# RightBar2_SchDoc.net
KiCad netlist of a schematic drawn in Altium Designer
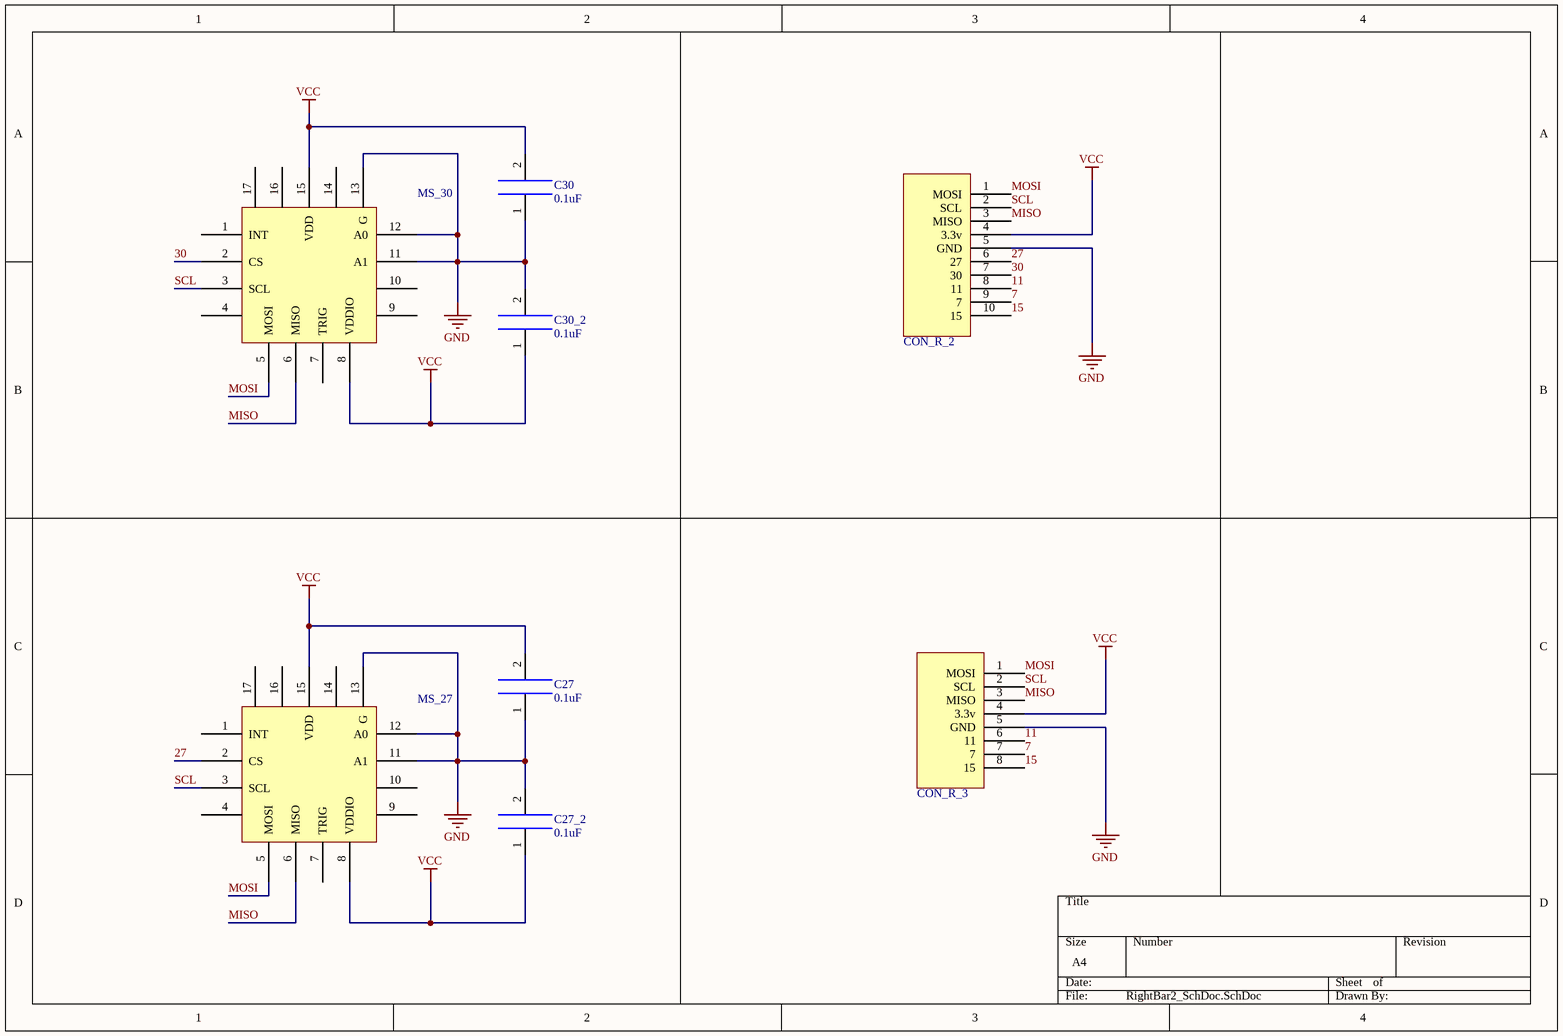
[diagram p0: RightBar2_SchDoc.SchDoc]

(export (version "E")
  (design (tool "Eeschema 10.0.6"))
  (components
    (comp (ref "C27")
      (value "0.1uF")
      (footprint "CAP_0603")
      (description "Capacitance")
      (libsource (lib "MagWaySchlib") (part "CAP"))
    )
    (comp (ref "C27_2")
      (value "0.1uF")
      (footprint "CAP_0603")
      (description "Capacitance")
      (libsource (lib "MagWaySchlib") (part "CAP"))
    )
    (comp (ref "C30")
      (value "0.1uF")
      (footprint "CAP_0603")
      (description "Capacitance")
      (libsource (lib "MagWaySchlib") (part "CAP"))
    )
    (comp (ref "C30_2")
      (value "0.1uF")
      (footprint "CAP_0603")
      (description "Capacitance")
      (libsource (lib "MagWaySchlib") (part "CAP"))
    )
    (comp (ref "CON_R_2")
      (value "PIN_right")
      (footprint "PIN_RIGHT_2")
      (libsource (lib "MagWaySchlib") (part "PIN_right_2"))
    )
    (comp (ref "CON_R_3")
      (value "PIN_right")
      (footprint "PIN_RIGHT_3")
      (libsource (lib "MagWaySchlib") (part "PIN_right_3"))
    )
    (comp (ref "MS_27")
      (value "MLX90393SLW ABA 011 RE")
      (footprint "MLX90393")
      (description "MLX90393 Sensor")
      (libsource (lib "MagWaySchlib") (part "MLX90393SLW ABA 011 RE"))
    )
    (comp (ref "MS_30")
      (value "MLX90393SLW ABA 011 RE")
      (footprint "MLX90393")
      (description "MLX90393 Sensor")
      (libsource (lib "MagWaySchlib") (part "MLX90393SLW ABA 011 RE"))
    )
  )
  (nets
    (net (code "1") (name "/7") (class "Default")
      (node (ref "CON_R_2") (pin "9") (pinfunction "7_9") (pintype "passive"))
      (node (ref "CON_R_3") (pin "7") (pinfunction "7_7") (pintype "passive"))
    )
    (net (code "2") (name "/11") (class "Default")
      (node (ref "CON_R_2") (pin "8") (pinfunction "11_8") (pintype "passive"))
      (node (ref "CON_R_3") (pin "6") (pinfunction "11_6") (pintype "passive"))
    )
    (net (code "3") (name "/15") (class "Default")
      (node (ref "CON_R_2") (pin "10") (pinfunction "15_10") (pintype "passive"))
      (node (ref "CON_R_3") (pin "8") (pinfunction "15_8") (pintype "passive"))
    )
    (net (code "4") (name "/27") (class "Default")
      (node (ref "CON_R_2") (pin "6") (pinfunction "27_6") (pintype "passive"))
      (node (ref "MS_27") (pin "2") (pinfunction "CS_2") (pintype "passive"))
    )
    (net (code "5") (name "/30") (class "Default")
      (node (ref "CON_R_2") (pin "7") (pinfunction "30_7") (pintype "passive"))
      (node (ref "MS_30") (pin "2") (pinfunction "CS_2") (pintype "passive"))
    )
    (net (code "6") (name "/MISO") (class "Default")
      (node (ref "CON_R_2") (pin "3") (pinfunction "MISO_3") (pintype "passive"))
      (node (ref "CON_R_3") (pin "3") (pinfunction "MISO_3") (pintype "passive"))
      (node (ref "MS_27") (pin "6") (pinfunction "MISO_6") (pintype "passive"))
      (node (ref "MS_30") (pin "6") (pinfunction "MISO_6") (pintype "passive"))
    )
    (net (code "7") (name "/MOSI") (class "Default")
      (node (ref "CON_R_2") (pin "1") (pinfunction "MOSI_1") (pintype "passive"))
      (node (ref "CON_R_3") (pin "1") (pinfunction "MOSI_1") (pintype "passive"))
      (node (ref "MS_27") (pin "5") (pinfunction "MOSI_5") (pintype "passive"))
      (node (ref "MS_30") (pin "5") (pinfunction "MOSI_5") (pintype "passive"))
    )
    (net (code "8") (name "/SCL") (class "Default")
      (node (ref "CON_R_2") (pin "2") (pinfunction "SCL_2") (pintype "passive"))
      (node (ref "CON_R_3") (pin "2") (pinfunction "SCL_2") (pintype "passive"))
      (node (ref "MS_27") (pin "3") (pinfunction "SCL_3") (pintype "passive"))
      (node (ref "MS_30") (pin "3") (pinfunction "SCL_3") (pintype "passive"))
    )
    (net (code "9") (name "GND") (class "Default")
      (node (ref "C27") (pin "1") (pintype "passive"))
      (node (ref "C27_2") (pin "2") (pintype "passive"))
      (node (ref "C30") (pin "1") (pintype "passive"))
      (node (ref "C30_2") (pin "2") (pintype "passive"))
      (node (ref "CON_R_2") (pin "5") (pinfunction "GND_5") (pintype "passive"))
      (node (ref "CON_R_3") (pin "5") (pinfunction "GND_5") (pintype "passive"))
      (node (ref "MS_27") (pin "11") (pinfunction "A1_11") (pintype "passive"))
      (node (ref "MS_27") (pin "12") (pinfunction "A0_12") (pintype "passive"))
      (node (ref "MS_27") (pin "13") (pinfunction "G_13") (pintype "passive"))
      (node (ref "MS_30") (pin "11") (pinfunction "A1_11") (pintype "passive"))
      (node (ref "MS_30") (pin "12") (pinfunction "A0_12") (pintype "passive"))
      (node (ref "MS_30") (pin "13") (pinfunction "G_13") (pintype "passive"))
    )
    (net (code "10") (name "VCC") (class "Default")
      (node (ref "C27") (pin "2") (pintype "passive"))
      (node (ref "C27_2") (pin "1") (pintype "passive"))
      (node (ref "C30") (pin "2") (pintype "passive"))
      (node (ref "C30_2") (pin "1") (pintype "passive"))
      (node (ref "CON_R_2") (pin "4") (pinfunction "3.3v_4") (pintype "passive"))
      (node (ref "CON_R_3") (pin "4") (pinfunction "3.3v_4") (pintype "passive"))
      (node (ref "MS_27") (pin "15") (pinfunction "VDD_15") (pintype "passive"))
      (node (ref "MS_27") (pin "8") (pinfunction "VDDIO_8") (pintype "passive"))
      (node (ref "MS_30") (pin "15") (pinfunction "VDD_15") (pintype "passive"))
      (node (ref "MS_30") (pin "8") (pinfunction "VDDIO_8") (pintype "passive"))
    )
    (net (code "11") (name "unconnected-(MS_27-INT-Pad1)") (class "Default")
      (node (ref "MS_27") (pin "1") (pinfunction "INT_1") (pintype "passive"))
    )
    (net (code "12") (name "unconnected-(MS_27-Pad4)") (class "Default")
      (node (ref "MS_27") (pin "4") (pintype "passive"))
    )
    (net (code "13") (name "unconnected-(MS_27-Pad9)") (class "Default")
      (node (ref "MS_27") (pin "9") (pintype "passive"))
    )
    (net (code "14") (name "unconnected-(MS_27-Pad10)") (class "Default")
      (node (ref "MS_27") (pin "10") (pintype "passive"))
    )
    (net (code "15") (name "unconnected-(MS_27-Pad14)") (class "Default")
      (node (ref "MS_27") (pin "14") (pintype "passive"))
    )
    (net (code "16") (name "unconnected-(MS_27-Pad16)") (class "Default")
      (node (ref "MS_27") (pin "16") (pintype "passive"))
    )
    (net (code "17") (name "unconnected-(MS_27-Pad17)") (class "Default")
      (node (ref "MS_27") (pin "17") (pintype "passive"))
    )
    (net (code "18") (name "unconnected-(MS_27-TRIG-Pad7)") (class "Default")
      (node (ref "MS_27") (pin "7") (pinfunction "TRIG_7") (pintype "passive"))
    )
    (net (code "19") (name "unconnected-(MS_30-INT-Pad1)") (class "Default")
      (node (ref "MS_30") (pin "1") (pinfunction "INT_1") (pintype "passive"))
    )
    (net (code "20") (name "unconnected-(MS_30-Pad4)") (class "Default")
      (node (ref "MS_30") (pin "4") (pintype "passive"))
    )
    (net (code "21") (name "unconnected-(MS_30-Pad9)") (class "Default")
      (node (ref "MS_30") (pin "9") (pintype "passive"))
    )
    (net (code "22") (name "unconnected-(MS_30-Pad10)") (class "Default")
      (node (ref "MS_30") (pin "10") (pintype "passive"))
    )
    (net (code "23") (name "unconnected-(MS_30-Pad14)") (class "Default")
      (node (ref "MS_30") (pin "14") (pintype "passive"))
    )
    (net (code "24") (name "unconnected-(MS_30-Pad16)") (class "Default")
      (node (ref "MS_30") (pin "16") (pintype "passive"))
    )
    (net (code "25") (name "unconnected-(MS_30-Pad17)") (class "Default")
      (node (ref "MS_30") (pin "17") (pintype "passive"))
    )
    (net (code "26") (name "unconnected-(MS_30-TRIG-Pad7)") (class "Default")
      (node (ref "MS_30") (pin "7") (pinfunction "TRIG_7") (pintype "passive"))
    )
  )
)
